# Atari_Punk_Console.net
KiCad netlist of a schematic drawn in EAGLE
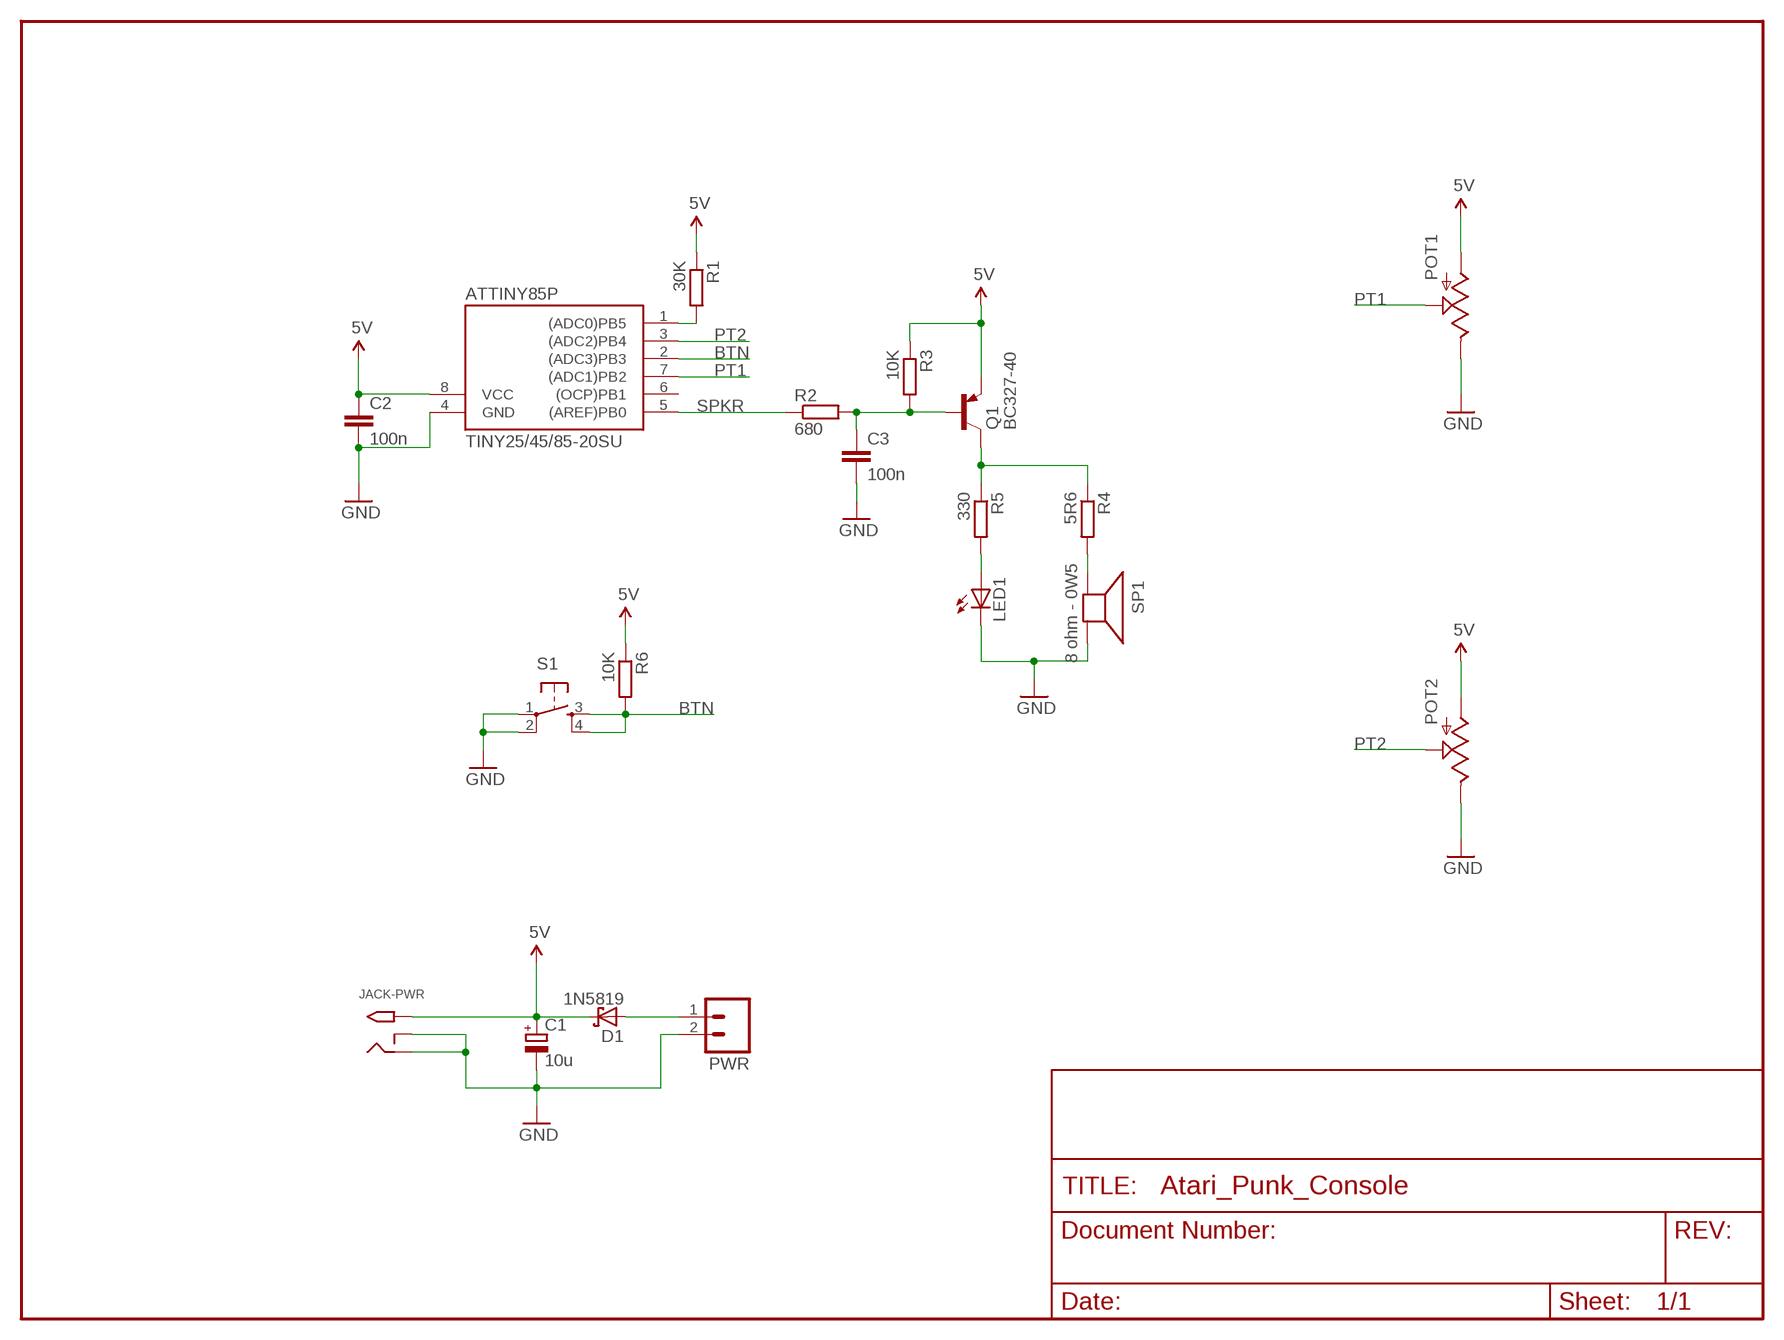
[diagram p0: schematic, sheet 1]

(export (version "E")
  (design (tool "Eeschema 10.0.6"))
  (components
    (comp (ref "ATTINY85P")
      (value "TINY25/45/85-20SU")
      (footprint "eagle-import:SOIC8")
      (libsource (lib "eagle-import") (part "TINY25/45/85-20SU"))
    )
    (comp (ref "C1")
      (value "10u")
      (footprint "eagle-import:E2,5-6")
      (libsource (lib "eagle-import") (part "CPOL-EUE2.5-6"))
    )
    (comp (ref "C2")
      (value "100n")
      (footprint "eagle-import:C025-025X050")
      (libsource (lib "eagle-import") (part "C-EU025-025X050"))
    )
    (comp (ref "C3")
      (value "100n")
      (footprint "eagle-import:C025-025X050")
      (libsource (lib "eagle-import") (part "C-EU025-025X050"))
    )
    (comp (ref "D1")
      (value "1N5819")
      (footprint "eagle-import:DO41-7")
      (libsource (lib "eagle-import") (part "SCHOTTKY-DIODEDO41-7"))
    )
    (comp (ref "JACK-PWR")
      (value "2.1MMJACKTHM")
      (footprint "eagle-import:PJ-102A")
      (libsource (lib "eagle-import") (part "2.1MMJACKTHM"))
    )
    (comp (ref "LED1")
      (value "LED5MM")
      (footprint "eagle-import:LED5MM")
      (libsource (lib "eagle-import") (part "LED5MM"))
    )
    (comp (ref "POT1")
      (value "POT")
      (footprint "eagle-import:ALPS_POT")
      (libsource (lib "eagle-import") (part "POT"))
    )
    (comp (ref "POT2")
      (value "POT")
      (footprint "eagle-import:ALPS_POT")
      (libsource (lib "eagle-import") (part "POT"))
    )
    (comp (ref "PWR")
      (value "M02LOCK")
      (footprint "eagle-import:1X02_LOCK")
      (libsource (lib "eagle-import") (part "M02LOCK"))
    )
    (comp (ref "Q1")
      (value "BC327-40")
      (footprint "eagle-import:TO92-EBC-OVAL")
      (libsource (lib "eagle-import") (part "2N2907"))
    )
    (comp (ref "R1")
      (value "30K")
      (footprint "eagle-import:0207_10")
      (libsource (lib "eagle-import") (part "R-EU_0207/10"))
    )
    (comp (ref "R2")
      (value "680")
      (footprint "eagle-import:0207_10")
      (libsource (lib "eagle-import") (part "R-EU_0207/10"))
    )
    (comp (ref "R3")
      (value "10K")
      (footprint "eagle-import:0207_10")
      (libsource (lib "eagle-import") (part "R-EU_0207/10"))
    )
    (comp (ref "R4")
      (value "5R6")
      (footprint "eagle-import:0207_10")
      (libsource (lib "eagle-import") (part "R-EU_0207/10"))
    )
    (comp (ref "R5")
      (value "330")
      (footprint "eagle-import:0207_10")
      (libsource (lib "eagle-import") (part "R-EU_0207/10"))
    )
    (comp (ref "R6")
      (value "10K")
      (footprint "eagle-import:0207_10")
      (libsource (lib "eagle-import") (part "R-EU_0207/10"))
    )
    (comp (ref "S1")
      (value "TAC_SWITCHPTH")
      (footprint "eagle-import:TACTILE-PTH")
      (libsource (lib "eagle-import") (part "TAC_SWITCHPTH"))
    )
    (comp (ref "SP1")
      (value "8 ohm - 0W5")
      (footprint "eagle-import:PS12")
      (libsource (lib "eagle-import") (part "SPEAKER/PS12"))
    )
  )
  (nets
    (net (code "1") (name "/BTN") (class "Default")
      (node (ref "ATTINY85P") (pin "2") (pinfunction "(ADC3)PB3_2") (pintype "bidirectional"))
      (node (ref "R6") (pin "2") (pinfunction "2_2") (pintype "passive"))
      (node (ref "S1") (pin "3") (pinfunction "3_3") (pintype "passive"))
      (node (ref "S1") (pin "4") (pinfunction "4_4") (pintype "passive"))
    )
    (net (code "2") (name "/PT1") (class "Default")
      (node (ref "ATTINY85P") (pin "7") (pinfunction "(ADC1)PB2_7") (pintype "bidirectional"))
      (node (ref "POT1") (pin "P$2") (pinfunction "S_P$2") (pintype "passive"))
    )
    (net (code "3") (name "/PT2") (class "Default")
      (node (ref "ATTINY85P") (pin "3") (pinfunction "(ADC2)PB4_3") (pintype "bidirectional"))
      (node (ref "POT2") (pin "P$2") (pinfunction "S_P$2") (pintype "passive"))
    )
    (net (code "4") (name "/SPKR") (class "Default")
      (node (ref "ATTINY85P") (pin "5") (pinfunction "(AREF)PB0_5") (pintype "bidirectional"))
      (node (ref "R2") (pin "1") (pinfunction "1_1") (pintype "passive"))
    )
    (net (code "5") (name "5V") (class "Default")
      (node (ref "ATTINY85P") (pin "8") (pinfunction "VCC_8") (pintype "power_in"))
      (node (ref "C1") (pin "+") (pinfunction "+_+") (pintype "passive"))
      (node (ref "C2") (pin "1") (pinfunction "1_1") (pintype "passive"))
      (node (ref "D1") (pin "C") (pinfunction "C_C") (pintype "passive"))
      (node (ref "JACK-PWR") (pin "TIP") (pinfunction "TIP_TIP") (pintype "bidirectional"))
      (node (ref "POT1") (pin "P$3") (pinfunction "A_P$3") (pintype "passive"))
      (node (ref "POT2") (pin "P$3") (pinfunction "A_P$3") (pintype "passive"))
      (node (ref "Q1") (pin "E") (pinfunction "E_E") (pintype "passive"))
      (node (ref "R1") (pin "1") (pinfunction "1_1") (pintype "passive"))
      (node (ref "R3") (pin "1") (pinfunction "1_1") (pintype "passive"))
      (node (ref "R6") (pin "1") (pinfunction "1_1") (pintype "passive"))
    )
    (net (code "6") (name "GND") (class "Default")
      (node (ref "ATTINY85P") (pin "4") (pinfunction "GND_4") (pintype "power_in"))
      (node (ref "C1") (pin "-") (pinfunction "-_-") (pintype "passive"))
      (node (ref "C2") (pin "2") (pinfunction "2_2") (pintype "passive"))
      (node (ref "C3") (pin "2") (pinfunction "2_2") (pintype "passive"))
      (node (ref "JACK-PWR") (pin "RING") (pinfunction "RING_RING") (pintype "bidirectional"))
      (node (ref "JACK-PWR") (pin "RING_SW") (pinfunction "RING_SW_RING_SW") (pintype "bidirectional"))
      (node (ref "LED1") (pin "K") (pinfunction "C_K") (pintype "passive"))
      (node (ref "POT1") (pin "P$1") (pinfunction "E_P$1") (pintype "passive"))
      (node (ref "POT2") (pin "P$1") (pinfunction "E_P$1") (pintype "passive"))
      (node (ref "PWR") (pin "2") (pinfunction "2_2") (pintype "passive"))
      (node (ref "S1") (pin "1") (pinfunction "1_1") (pintype "passive"))
      (node (ref "S1") (pin "2") (pinfunction "2_2") (pintype "passive"))
      (node (ref "SP1") (pin "P$2") (pinfunction "-_P$2") (pintype "passive"))
    )
    (net (code "7") (name "Net-(ATTINY85P-(ADC0)PB5)") (class "Default")
      (node (ref "ATTINY85P") (pin "1") (pinfunction "(ADC0)PB5_1") (pintype "bidirectional"))
      (node (ref "R1") (pin "2") (pinfunction "2_2") (pintype "passive"))
    )
    (net (code "8") (name "Net-(C3-Pad1)") (class "Default")
      (node (ref "C3") (pin "1") (pinfunction "1_1") (pintype "passive"))
      (node (ref "Q1") (pin "B") (pinfunction "B_B") (pintype "passive"))
      (node (ref "R2") (pin "2") (pinfunction "2_2") (pintype "passive"))
      (node (ref "R3") (pin "2") (pinfunction "2_2") (pintype "passive"))
    )
    (net (code "9") (name "Net-(D1-PadA)") (class "Default")
      (node (ref "D1") (pin "A") (pinfunction "A_A") (pintype "passive"))
      (node (ref "PWR") (pin "1") (pinfunction "1_1") (pintype "passive"))
    )
    (net (code "10") (name "Net-(LED1-PadA)") (class "Default")
      (node (ref "LED1") (pin "A") (pinfunction "A_A") (pintype "passive"))
      (node (ref "R5") (pin "2") (pinfunction "2_2") (pintype "passive"))
    )
    (net (code "11") (name "Net-(Q1-PadC)") (class "Default")
      (node (ref "Q1") (pin "C") (pinfunction "C_C") (pintype "passive"))
      (node (ref "R4") (pin "1") (pinfunction "1_1") (pintype "passive"))
      (node (ref "R5") (pin "1") (pinfunction "1_1") (pintype "passive"))
    )
    (net (code "12") (name "Net-(SP1-+)") (class "Default")
      (node (ref "R4") (pin "2") (pinfunction "2_2") (pintype "passive"))
      (node (ref "SP1") (pin "P$1") (pinfunction "+_P$1") (pintype "passive"))
    )
    (net (code "13") (name "unconnected-(ATTINY85P-(OCP)PB1-Pad6)") (class "Default")
      (node (ref "ATTINY85P") (pin "6") (pinfunction "(OCP)PB1_6") (pintype "bidirectional"))
    )
  )
)
